# 7seg.net
KiCad netlist of a schematic drawn in EAGLE
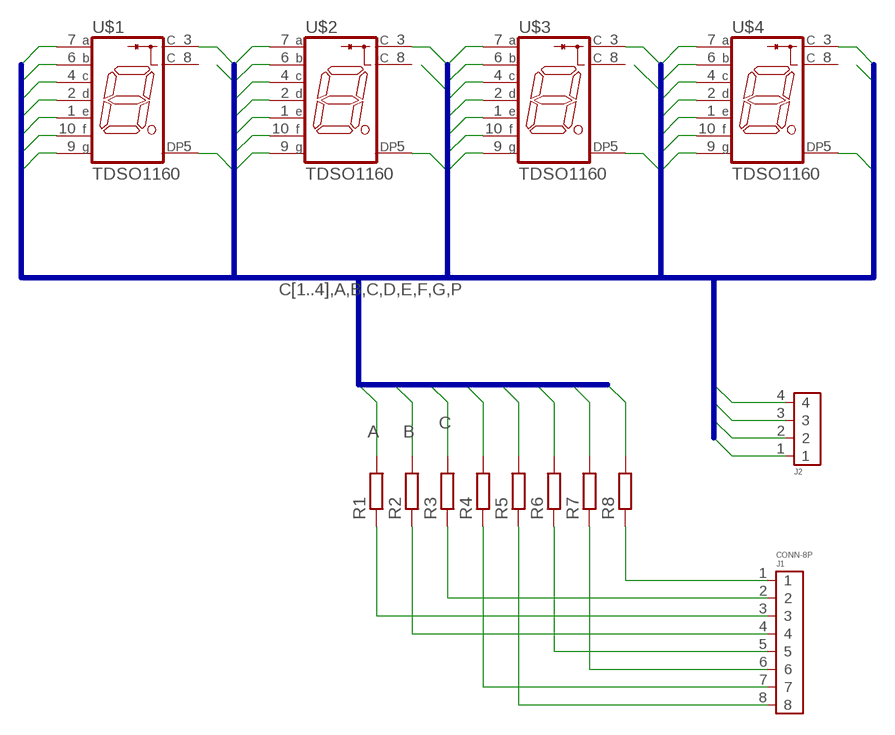
[diagram p0: schematic, sheet 1]

(export (version "E")
  (design (tool "Eeschema 10.0.6"))
  (components
    (comp (ref "J1")
      (value "CONN-8P")
      (footprint "eagle-import:CONN-8P")
      (libsource (lib "eagle-import") (part "CONN-8P"))
    )
    (comp (ref "J2")
      (value "CONN-4P-4P")
      (footprint "eagle-import:CONN-4P")
      (libsource (lib "eagle-import") (part "CONN-4P-4P"))
    )
    (comp (ref "R1")
      (value "R0202/7-V")
      (footprint "eagle-import:0202_7-V")
      (libsource (lib "eagle-import") (part "R0202/7-V"))
    )
    (comp (ref "R2")
      (value "R0202/7-V")
      (footprint "eagle-import:0202_7-V")
      (libsource (lib "eagle-import") (part "R0202/7-V"))
    )
    (comp (ref "R3")
      (value "R0202/7-V")
      (footprint "eagle-import:0202_7-V")
      (libsource (lib "eagle-import") (part "R0202/7-V"))
    )
    (comp (ref "R4")
      (value "R0202/7-V")
      (footprint "eagle-import:0202_7-V")
      (libsource (lib "eagle-import") (part "R0202/7-V"))
    )
    (comp (ref "R5")
      (value "R0202/7-V")
      (footprint "eagle-import:0202_7-V")
      (libsource (lib "eagle-import") (part "R0202/7-V"))
    )
    (comp (ref "R6")
      (value "R0202/7-V")
      (footprint "eagle-import:0202_7-V")
      (libsource (lib "eagle-import") (part "R0202/7-V"))
    )
    (comp (ref "R7")
      (value "R0202/7-V")
      (footprint "eagle-import:0202_7-V")
      (libsource (lib "eagle-import") (part "R0202/7-V"))
    )
    (comp (ref "R8")
      (value "R0202/7-V")
      (footprint "eagle-import:0202_7-V")
      (libsource (lib "eagle-import") (part "R0202/7-V"))
    )
    (comp (ref "U$1")
      (value "TDSO1160")
      (footprint "eagle-import:TDSX1150")
      (libsource (lib "eagle-import") (part "TDSO1160"))
    )
    (comp (ref "U$2")
      (value "TDSO1160")
      (footprint "eagle-import:TDSX1150")
      (libsource (lib "eagle-import") (part "TDSO1160"))
    )
    (comp (ref "U$3")
      (value "TDSO1160")
      (footprint "eagle-import:TDSX1150")
      (libsource (lib "eagle-import") (part "TDSO1160"))
    )
    (comp (ref "U$4")
      (value "TDSO1160")
      (footprint "eagle-import:TDSX1150")
      (libsource (lib "eagle-import") (part "TDSO1160"))
    )
  )
  (nets
    (net (code "1") (name "/A") (class "Default")
      (node (ref "R1") (pin "2") (pinfunction "2_2") (pintype "passive"))
      (node (ref "U$1") (pin "7") (pinfunction "A_7") (pintype "passive"))
      (node (ref "U$2") (pin "7") (pinfunction "A_7") (pintype "passive"))
      (node (ref "U$3") (pin "7") (pinfunction "A_7") (pintype "passive"))
      (node (ref "U$4") (pin "7") (pinfunction "A_7") (pintype "passive"))
    )
    (net (code "2") (name "/B") (class "Default")
      (node (ref "R2") (pin "2") (pinfunction "2_2") (pintype "passive"))
      (node (ref "U$1") (pin "6") (pinfunction "B_6") (pintype "passive"))
      (node (ref "U$2") (pin "6") (pinfunction "B_6") (pintype "passive"))
      (node (ref "U$3") (pin "6") (pinfunction "B_6") (pintype "passive"))
      (node (ref "U$4") (pin "6") (pinfunction "B_6") (pintype "passive"))
    )
    (net (code "3") (name "/C") (class "Default")
      (node (ref "R3") (pin "2") (pinfunction "2_2") (pintype "passive"))
      (node (ref "U$1") (pin "4") (pinfunction "C_4") (pintype "passive"))
      (node (ref "U$2") (pin "4") (pinfunction "C_4") (pintype "passive"))
      (node (ref "U$3") (pin "4") (pinfunction "C_4") (pintype "passive"))
      (node (ref "U$4") (pin "4") (pinfunction "C_4") (pintype "passive"))
    )
    (net (code "4") (name "/C1") (class "Default")
      (node (ref "J2") (pin "1") (pinfunction "1_1") (pintype "bidirectional"))
      (node (ref "U$1") (pin "3") (pinfunction "C_3") (pintype "passive"))
    )
    (net (code "5") (name "/C2") (class "Default")
      (node (ref "J2") (pin "2") (pinfunction "2_2") (pintype "bidirectional"))
      (node (ref "U$2") (pin "3") (pinfunction "C_3") (pintype "passive"))
    )
    (net (code "6") (name "/C3") (class "Default")
      (node (ref "J2") (pin "3") (pinfunction "3_3") (pintype "bidirectional"))
      (node (ref "U$3") (pin "3") (pinfunction "C_3") (pintype "passive"))
    )
    (net (code "7") (name "/C4") (class "Default")
      (node (ref "J2") (pin "4") (pinfunction "4_4") (pintype "bidirectional"))
      (node (ref "U$4") (pin "3") (pinfunction "C_3") (pintype "passive"))
    )
    (net (code "8") (name "/D") (class "Default")
      (node (ref "R4") (pin "2") (pinfunction "2_2") (pintype "passive"))
      (node (ref "U$1") (pin "2") (pinfunction "D_2") (pintype "passive"))
      (node (ref "U$2") (pin "2") (pinfunction "D_2") (pintype "passive"))
      (node (ref "U$3") (pin "2") (pinfunction "D_2") (pintype "passive"))
      (node (ref "U$4") (pin "2") (pinfunction "D_2") (pintype "passive"))
    )
    (net (code "9") (name "/E") (class "Default")
      (node (ref "R5") (pin "2") (pinfunction "2_2") (pintype "passive"))
      (node (ref "U$1") (pin "1") (pinfunction "E_1") (pintype "passive"))
      (node (ref "U$2") (pin "1") (pinfunction "E_1") (pintype "passive"))
      (node (ref "U$3") (pin "1") (pinfunction "E_1") (pintype "passive"))
      (node (ref "U$4") (pin "1") (pinfunction "E_1") (pintype "passive"))
    )
    (net (code "10") (name "/F") (class "Default")
      (node (ref "R6") (pin "2") (pinfunction "2_2") (pintype "passive"))
      (node (ref "U$1") (pin "10") (pinfunction "F_10") (pintype "passive"))
      (node (ref "U$2") (pin "10") (pinfunction "F_10") (pintype "passive"))
      (node (ref "U$3") (pin "10") (pinfunction "F_10") (pintype "passive"))
      (node (ref "U$4") (pin "10") (pinfunction "F_10") (pintype "passive"))
    )
    (net (code "11") (name "/G") (class "Default")
      (node (ref "R7") (pin "2") (pinfunction "2_2") (pintype "passive"))
      (node (ref "U$1") (pin "9") (pinfunction "G_9") (pintype "passive"))
      (node (ref "U$2") (pin "9") (pinfunction "G_9") (pintype "passive"))
      (node (ref "U$3") (pin "9") (pinfunction "G_9") (pintype "passive"))
      (node (ref "U$4") (pin "9") (pinfunction "G_9") (pintype "passive"))
    )
    (net (code "12") (name "/P") (class "Default")
      (node (ref "R8") (pin "2") (pinfunction "2_2") (pintype "passive"))
      (node (ref "U$1") (pin "5") (pinfunction "DP_5") (pintype "passive"))
      (node (ref "U$2") (pin "5") (pinfunction "DP_5") (pintype "passive"))
      (node (ref "U$3") (pin "5") (pinfunction "DP_5") (pintype "passive"))
      (node (ref "U$4") (pin "5") (pinfunction "DP_5") (pintype "passive"))
    )
    (net (code "14") (name "Net-(J1-Pad1)") (class "Default")
      (node (ref "J1") (pin "1") (pinfunction "1_1") (pintype "passive"))
      (node (ref "R8") (pin "1") (pinfunction "1_1") (pintype "passive"))
    )
    (net (code "15") (name "Net-(J1-Pad2)") (class "Default")
      (node (ref "J1") (pin "2") (pinfunction "2_2") (pintype "passive"))
      (node (ref "R3") (pin "1") (pinfunction "1_1") (pintype "passive"))
    )
    (net (code "16") (name "Net-(J1-Pad3)") (class "Default")
      (node (ref "J1") (pin "3") (pinfunction "3_3") (pintype "passive"))
      (node (ref "R1") (pin "1") (pinfunction "1_1") (pintype "passive"))
    )
    (net (code "17") (name "Net-(J1-Pad4)") (class "Default")
      (node (ref "J1") (pin "4") (pinfunction "4_4") (pintype "passive"))
      (node (ref "R2") (pin "1") (pinfunction "1_1") (pintype "passive"))
    )
    (net (code "18") (name "Net-(J1-Pad5)") (class "Default")
      (node (ref "J1") (pin "5") (pinfunction "5_5") (pintype "passive"))
      (node (ref "R6") (pin "1") (pinfunction "1_1") (pintype "passive"))
    )
    (net (code "19") (name "Net-(J1-Pad6)") (class "Default")
      (node (ref "J1") (pin "6") (pinfunction "6_6") (pintype "passive"))
      (node (ref "R7") (pin "1") (pinfunction "1_1") (pintype "passive"))
    )
    (net (code "20") (name "Net-(J1-Pad7)") (class "Default")
      (node (ref "J1") (pin "7") (pinfunction "7_7") (pintype "passive"))
      (node (ref "R4") (pin "1") (pinfunction "1_1") (pintype "passive"))
    )
    (net (code "21") (name "Net-(J1-Pad8)") (class "Default")
      (node (ref "J1") (pin "8") (pinfunction "8_8") (pintype "passive"))
      (node (ref "R5") (pin "1") (pinfunction "1_1") (pintype "passive"))
    )
    (net (code "22") (name "unconnected-(U$1-C-Pad8)") (class "Default")
      (node (ref "U$1") (pin "8") (pinfunction "C_8") (pintype "passive"))
    )
    (net (code "23") (name "unconnected-(U$2-C-Pad8)") (class "Default")
      (node (ref "U$2") (pin "8") (pinfunction "C_8") (pintype "passive"))
    )
    (net (code "24") (name "unconnected-(U$3-C-Pad8)") (class "Default")
      (node (ref "U$3") (pin "8") (pinfunction "C_8") (pintype "passive"))
    )
    (net (code "25") (name "unconnected-(U$4-C-Pad8)") (class "Default")
      (node (ref "U$4") (pin "8") (pinfunction "C_8") (pintype "passive"))
    )
  )
)
